# tiny_board.net
KiCad netlist of a schematic drawn in EAGLE
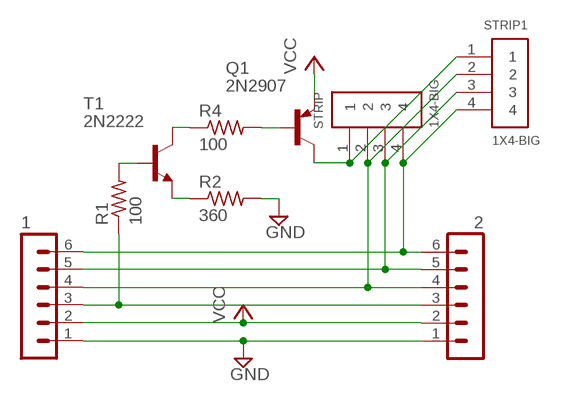
[diagram p0: schematic, sheet 1]

(export (version "E")
  (design (tool "Eeschema 10.0.6"))
  (components
    (comp (ref "1")
      (value "MA06-1")
      (footprint "eagle-import:MA06-1")
      (libsource (lib "eagle-import") (part "MA06-1"))
    )
    (comp (ref "2")
      (value "MA06-1")
      (footprint "eagle-import:MA06-1")
      (libsource (lib "eagle-import") (part "MA06-1"))
    )
    (comp (ref "Q1")
      (value "2N2907")
      (footprint "eagle-import:TO92-EBC-OVAL")
      (libsource (lib "eagle-import") (part "2N2907"))
    )
    (comp (ref "R1")
      (value "100")
      (footprint "eagle-import:0207_10")
      (libsource (lib "eagle-import") (part "R-US_0207/10"))
    )
    (comp (ref "R2")
      (value "360")
      (footprint "eagle-import:0207_10")
      (libsource (lib "eagle-import") (part "R-US_0207/10"))
    )
    (comp (ref "R4")
      (value "100")
      (footprint "eagle-import:0207_10")
      (libsource (lib "eagle-import") (part "R-US_0207/10"))
    )
    (comp (ref "STRIP")
      (value "1X4-BIG")
      (footprint "eagle-import:1X04-BIG")
      (libsource (lib "eagle-import") (part "1X4-BIG"))
    )
    (comp (ref "STRIP1")
      (value "1X4-BIG")
      (footprint "eagle-import:1X04-BIG")
      (libsource (lib "eagle-import") (part "1X4-BIG"))
    )
    (comp (ref "T1")
      (value "2N2222")
      (footprint "eagle-import:TO92-EBC-OVAL")
      (libsource (lib "eagle-import") (part "2N2222"))
    )
  )
  (nets
    (net (code "1") (name "GND") (class "Default")
      (node (ref "1") (pin "1") (pinfunction "1_1") (pintype "passive"))
      (node (ref "2") (pin "1") (pinfunction "1_1") (pintype "passive"))
      (node (ref "R2") (pin "2") (pinfunction "2_2") (pintype "passive"))
    )
    (net (code "2") (name "Net-(1-Pad3)") (class "Default")
      (node (ref "1") (pin "3") (pinfunction "3_3") (pintype "passive"))
      (node (ref "2") (pin "3") (pinfunction "3_3") (pintype "passive"))
      (node (ref "R1") (pin "1") (pinfunction "1_1") (pintype "passive"))
    )
    (net (code "3") (name "Net-(1-Pad4)") (class "Default")
      (node (ref "1") (pin "4") (pinfunction "4_4") (pintype "passive"))
      (node (ref "2") (pin "4") (pinfunction "4_4") (pintype "passive"))
      (node (ref "STRIP") (pin "2") (pinfunction "2_2") (pintype "bidirectional"))
      (node (ref "STRIP1") (pin "2") (pinfunction "2_2") (pintype "bidirectional"))
    )
    (net (code "4") (name "Net-(1-Pad5)") (class "Default")
      (node (ref "1") (pin "5") (pinfunction "5_5") (pintype "passive"))
      (node (ref "2") (pin "5") (pinfunction "5_5") (pintype "passive"))
      (node (ref "STRIP") (pin "3") (pinfunction "3_3") (pintype "bidirectional"))
      (node (ref "STRIP1") (pin "3") (pinfunction "3_3") (pintype "bidirectional"))
    )
    (net (code "5") (name "Net-(1-Pad6)") (class "Default")
      (node (ref "1") (pin "6") (pinfunction "6_6") (pintype "passive"))
      (node (ref "2") (pin "6") (pinfunction "6_6") (pintype "passive"))
      (node (ref "STRIP") (pin "4") (pinfunction "4_4") (pintype "bidirectional"))
      (node (ref "STRIP1") (pin "4") (pinfunction "4_4") (pintype "bidirectional"))
    )
    (net (code "6") (name "Net-(Q1-PadB)") (class "Default")
      (node (ref "Q1") (pin "B") (pinfunction "B_B") (pintype "passive"))
      (node (ref "R4") (pin "2") (pinfunction "2_2") (pintype "passive"))
    )
    (net (code "7") (name "Net-(Q1-PadC)") (class "Default")
      (node (ref "Q1") (pin "C") (pinfunction "C_C") (pintype "passive"))
      (node (ref "STRIP") (pin "1") (pinfunction "1_1") (pintype "bidirectional"))
      (node (ref "STRIP1") (pin "1") (pinfunction "1_1") (pintype "bidirectional"))
    )
    (net (code "8") (name "Net-(R1-Pad2)") (class "Default")
      (node (ref "R1") (pin "2") (pinfunction "2_2") (pintype "passive"))
      (node (ref "T1") (pin "B") (pinfunction "B_B") (pintype "passive"))
    )
    (net (code "9") (name "Net-(R2-Pad1)") (class "Default")
      (node (ref "R2") (pin "1") (pinfunction "1_1") (pintype "passive"))
      (node (ref "T1") (pin "E") (pinfunction "E_E") (pintype "passive"))
    )
    (net (code "10") (name "Net-(R4-Pad1)") (class "Default")
      (node (ref "R4") (pin "1") (pinfunction "1_1") (pintype "passive"))
      (node (ref "T1") (pin "C") (pinfunction "C_C") (pintype "passive"))
    )
    (net (code "11") (name "VCC") (class "Default")
      (node (ref "1") (pin "2") (pinfunction "2_2") (pintype "passive"))
      (node (ref "2") (pin "2") (pinfunction "2_2") (pintype "passive"))
      (node (ref "Q1") (pin "E") (pinfunction "E_E") (pintype "passive"))
    )
  )
)
